# main.net
KiCad netlist of a schematic drawn in EAGLE
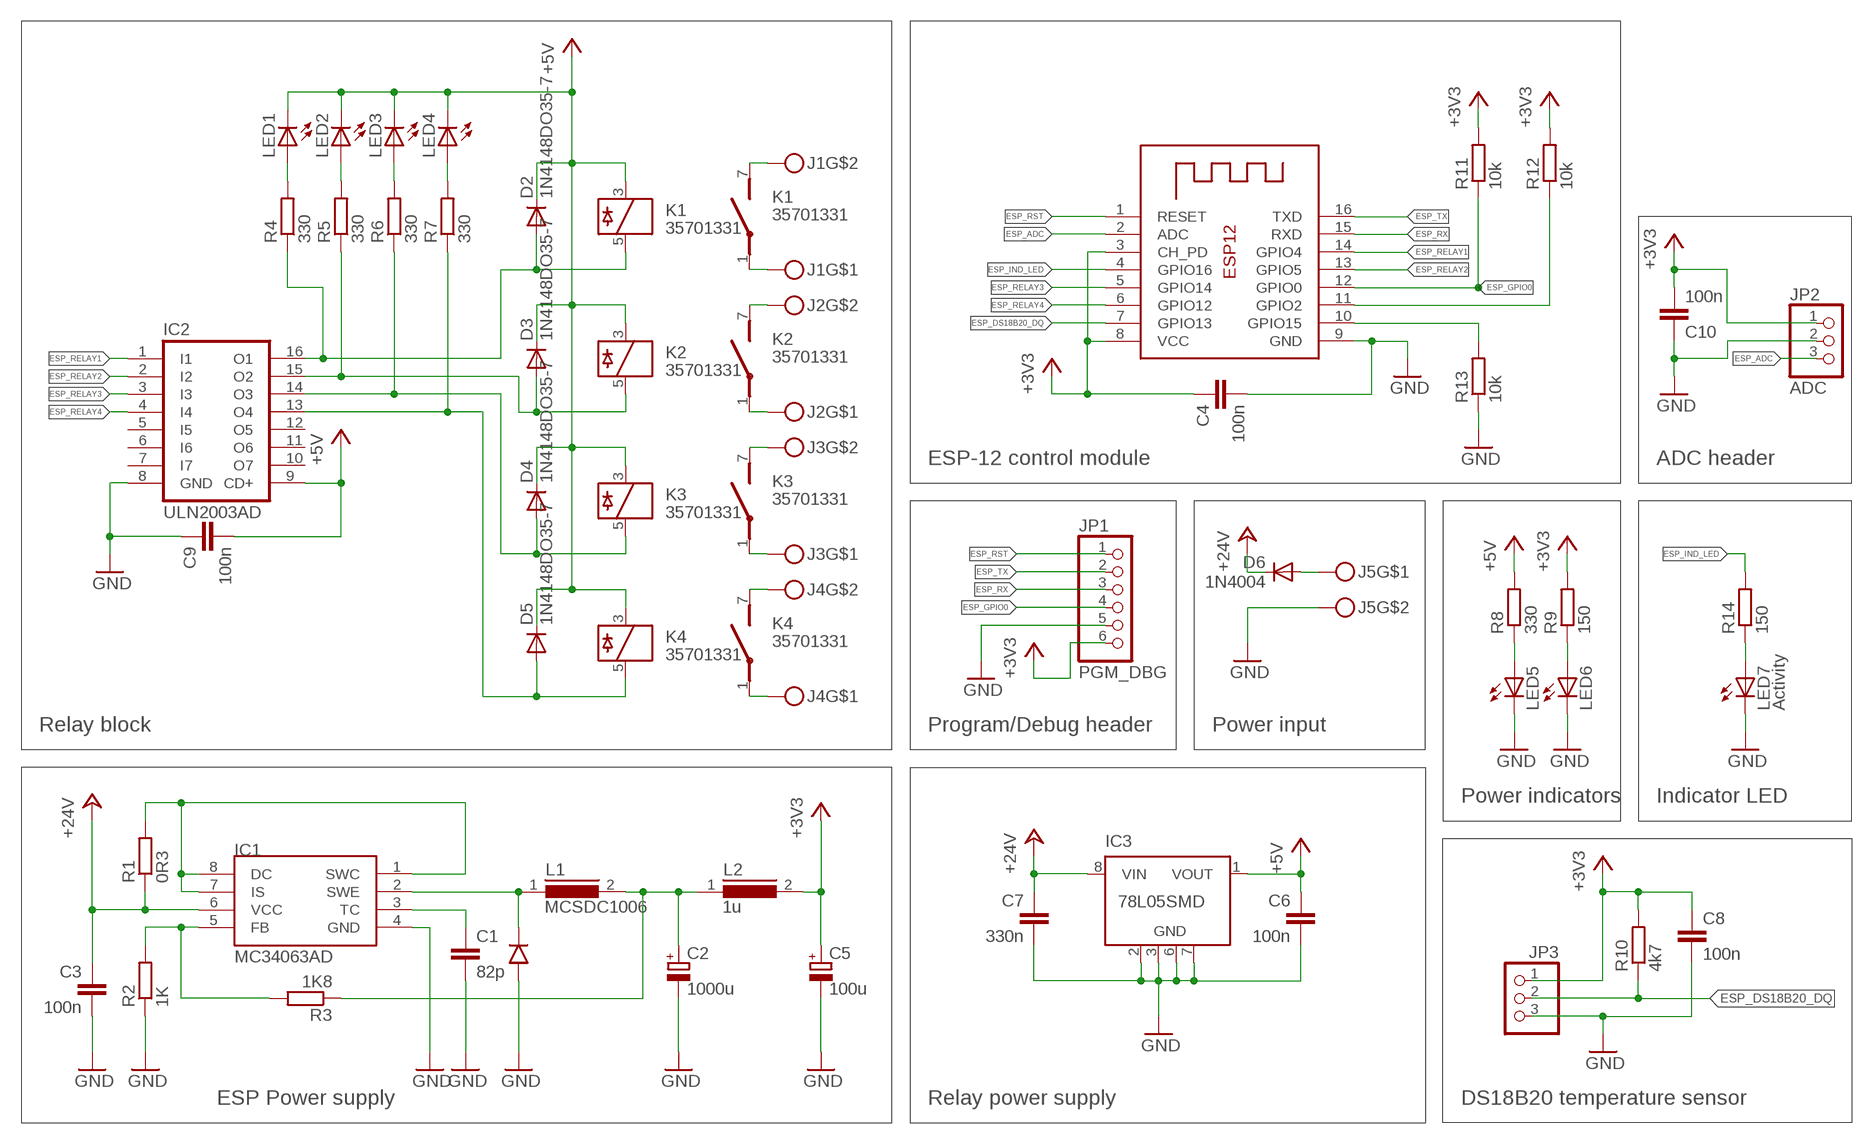
[diagram p0: schematic, sheet 1]

(export (version "E")
  (design (tool "Eeschema 10.0.6"))
  (components
    (comp (ref "C1")
      (value "82p")
      (footprint "eagle-import:C1206")
      (libsource (lib "eagle-import") (part "C-EUC1206"))
    )
    (comp (ref "C2")
      (value "1000u")
      (footprint "eagle-import:UD-10X10_NICHICON")
      (libsource (lib "eagle-import") (part "CPOL-EUUD-10X10"))
    )
    (comp (ref "C3")
      (value "100n")
      (footprint "eagle-import:C1206")
      (libsource (lib "eagle-import") (part "C-EUC1206"))
    )
    (comp (ref "C4")
      (value "100n")
      (footprint "eagle-import:C1206")
      (libsource (lib "eagle-import") (part "C-EUC1206"))
    )
    (comp (ref "C5")
      (value "100u")
      (footprint "eagle-import:153CLV-0807")
      (libsource (lib "eagle-import") (part "CPOL-EU153CLV-0807"))
    )
    (comp (ref "C6")
      (value "100n")
      (footprint "eagle-import:C1206")
      (libsource (lib "eagle-import") (part "C-EUC1206"))
    )
    (comp (ref "C7")
      (value "330n")
      (footprint "eagle-import:C1206")
      (libsource (lib "eagle-import") (part "C-EUC1206"))
    )
    (comp (ref "C8")
      (value "100n")
      (footprint "eagle-import:C1206")
      (libsource (lib "eagle-import") (part "C-EUC1206"))
    )
    (comp (ref "C9")
      (value "100n")
      (footprint "eagle-import:C1206")
      (libsource (lib "eagle-import") (part "C-EUC1206"))
    )
    (comp (ref "C10")
      (value "100n")
      (footprint "eagle-import:C1206")
      (libsource (lib "eagle-import") (part "C-EUC1206"))
    )
    (comp (ref "D1")
      (value "1N5819HW")
      (footprint "eagle-import:SOD123")
      (fields (field (name "MF") "DIODES INC.") (field (name "MPN") "1N5819HW-7-F"))
      (libsource (lib "eagle-import") (part "1N5819HW"))
    )
    (comp (ref "D2")
      (value "1N4148DO35-7")
      (footprint "eagle-import:DO35-7")
      (libsource (lib "eagle-import") (part "1N4148DO35-7"))
    )
    (comp (ref "D3")
      (value "1N4148DO35-7")
      (footprint "eagle-import:DO35-7")
      (libsource (lib "eagle-import") (part "1N4148DO35-7"))
    )
    (comp (ref "D4")
      (value "1N4148DO35-7")
      (footprint "eagle-import:DO35-7")
      (libsource (lib "eagle-import") (part "1N4148DO35-7"))
    )
    (comp (ref "D5")
      (value "1N4148DO35-7")
      (footprint "eagle-import:DO35-7")
      (libsource (lib "eagle-import") (part "1N4148DO35-7"))
    )
    (comp (ref "D6")
      (value "1N4004")
      (footprint "eagle-import:DO41-10")
      (libsource (lib "eagle-import") (part "1N4004"))
    )
    (comp (ref "IC1")
      (value "MC34063AD")
      (footprint "eagle-import:SOIC8")
      (libsource (lib "eagle-import") (part "MC34063AD"))
    )
    (comp (ref "IC2")
      (value "ULN2003AD")
      (footprint "eagle-import:SO16")
      (libsource (lib "eagle-import") (part "ULN2003AD"))
    )
    (comp (ref "IC3")
      (value "78L05SMD")
      (footprint "eagle-import:SO08")
      (libsource (lib "eagle-import") (part "78LSMD05"))
    )
    (comp (ref "J1")
      (value "SCREW-TERMINAL-2PIN")
      (footprint "eagle-import:PITCH4.3-PIN2")
      (libsource (lib "eagle-import") (part "SCREW-TERMINAL-2PIN"))
    )
    (comp (ref "J2")
      (value "SCREW-TERMINAL-2PIN")
      (footprint "eagle-import:PITCH4.3-PIN2")
      (libsource (lib "eagle-import") (part "SCREW-TERMINAL-2PIN"))
    )
    (comp (ref "J3")
      (value "SCREW-TERMINAL-2PIN")
      (footprint "eagle-import:PITCH4.3-PIN2")
      (libsource (lib "eagle-import") (part "SCREW-TERMINAL-2PIN"))
    )
    (comp (ref "J4")
      (value "SCREW-TERMINAL-2PIN")
      (footprint "eagle-import:PITCH4.3-PIN2")
      (libsource (lib "eagle-import") (part "SCREW-TERMINAL-2PIN"))
    )
    (comp (ref "J5")
      (value "PWR_IN")
      (footprint "eagle-import:PITCH4.3-PIN2")
      (libsource (lib "eagle-import") (part "SCREW-TERMINAL-2PIN"))
    )
    (comp (ref "JP1")
      (value "PGM_DBG")
      (footprint "eagle-import:1X06")
      (libsource (lib "eagle-import") (part "PINHD-1X6"))
    )
    (comp (ref "JP2")
      (value "ADC")
      (footprint "eagle-import:1X03")
      (libsource (lib "eagle-import") (part "PINHD-1X3"))
    )
    (comp (ref "JP3")
      (value "PINHD-1X3")
      (footprint "eagle-import:1X03")
      (libsource (lib "eagle-import") (part "PINHD-1X3"))
    )
    (comp (ref "K1")
      (value "35701331")
      (footprint "eagle-import:REED")
      (libsource (lib "eagle-import") (part "35701331"))
    )
    (comp (ref "K2")
      (value "35701331")
      (footprint "eagle-import:REED")
      (libsource (lib "eagle-import") (part "35701331"))
    )
    (comp (ref "K3")
      (value "35701331")
      (footprint "eagle-import:REED")
      (libsource (lib "eagle-import") (part "35701331"))
    )
    (comp (ref "K4")
      (value "35701331")
      (footprint "eagle-import:REED")
      (libsource (lib "eagle-import") (part "35701331"))
    )
    (comp (ref "L1")
      (value "MCSDC1006")
      (footprint "eagle-import:SMD")
      (libsource (lib "eagle-import") (part "MCSDC1006"))
    )
    (comp (ref "L2")
      (value "1u")
      (footprint "eagle-import:R1210")
      (libsource (lib "eagle-import") (part "SMD1210"))
    )
    (comp (ref "LED1")
      (value "LED5MM")
      (footprint "eagle-import:LED5MM")
      (libsource (lib "eagle-import") (part "LED5MM"))
    )
    (comp (ref "LED2")
      (value "LED5MM")
      (footprint "eagle-import:LED5MM")
      (libsource (lib "eagle-import") (part "LED5MM"))
    )
    (comp (ref "LED3")
      (value "LED5MM")
      (footprint "eagle-import:LED5MM")
      (libsource (lib "eagle-import") (part "LED5MM"))
    )
    (comp (ref "LED4")
      (value "LED5MM")
      (footprint "eagle-import:LED5MM")
      (libsource (lib "eagle-import") (part "LED5MM"))
    )
    (comp (ref "LED5")
      (value "LED5MM")
      (footprint "eagle-import:LED5MM")
      (libsource (lib "eagle-import") (part "LED5MM"))
    )
    (comp (ref "LED6")
      (value "LED5MM")
      (footprint "eagle-import:LED5MM")
      (libsource (lib "eagle-import") (part "LED5MM"))
    )
    (comp (ref "LED7")
      (value "Activity")
      (footprint "eagle-import:LED5MM")
      (libsource (lib "eagle-import") (part "LED5MM"))
    )
    (comp (ref "R1")
      (value "0R3")
      (footprint "eagle-import:R1206")
      (libsource (lib "eagle-import") (part "R-EU_R1206"))
    )
    (comp (ref "R2")
      (value "1K")
      (footprint "eagle-import:R1206")
      (libsource (lib "eagle-import") (part "R-EU_R1206"))
    )
    (comp (ref "R3")
      (value "1K8")
      (footprint "eagle-import:R1206")
      (libsource (lib "eagle-import") (part "R-EU_R1206"))
    )
    (comp (ref "R4")
      (value "330")
      (footprint "eagle-import:R1206")
      (libsource (lib "eagle-import") (part "R-EU_R1206"))
    )
    (comp (ref "R5")
      (value "330")
      (footprint "eagle-import:R1206")
      (libsource (lib "eagle-import") (part "R-EU_R1206"))
    )
    (comp (ref "R6")
      (value "330")
      (footprint "eagle-import:R1206")
      (libsource (lib "eagle-import") (part "R-EU_R1206"))
    )
    (comp (ref "R7")
      (value "330")
      (footprint "eagle-import:R1206")
      (libsource (lib "eagle-import") (part "R-EU_R1206"))
    )
    (comp (ref "R8")
      (value "330")
      (footprint "eagle-import:R1206")
      (libsource (lib "eagle-import") (part "R-EU_R1206"))
    )
    (comp (ref "R9")
      (value "150")
      (footprint "eagle-import:R1206")
      (libsource (lib "eagle-import") (part "R-EU_R1206"))
    )
    (comp (ref "R10")
      (value "4k7")
      (footprint "eagle-import:R1206")
      (libsource (lib "eagle-import") (part "R-EU_R1206"))
    )
    (comp (ref "R11")
      (value "10k")
      (footprint "eagle-import:R1206")
      (libsource (lib "eagle-import") (part "R-EU_R1206"))
    )
    (comp (ref "R12")
      (value "10k")
      (footprint "eagle-import:R1206")
      (libsource (lib "eagle-import") (part "R-EU_R1206"))
    )
    (comp (ref "R13")
      (value "10k")
      (footprint "eagle-import:R1206")
      (libsource (lib "eagle-import") (part "R-EU_R1206"))
    )
    (comp (ref "R14")
      (value "150")
      (footprint "eagle-import:R1206")
      (libsource (lib "eagle-import") (part "R-EU_R1206"))
    )
    (comp (ref "X1")
      (value "ESP-12")
      (footprint "eagle-import:ESP-12")
      (libsource (lib "eagle-import") (part "ESP-12"))
    )
  )
  (nets
    (net (code "1") (name "+3V3") (class "Default")
      (node (ref "C10") (pin "2") (pinfunction "2_2") (pintype "passive"))
      (node (ref "C4") (pin "1") (pinfunction "1_1") (pintype "passive"))
      (node (ref "C5") (pin "+") (pinfunction "+_+") (pintype "passive"))
      (node (ref "C8") (pin "1") (pinfunction "1_1") (pintype "passive"))
      (node (ref "JP1") (pin "6") (pinfunction "6_6") (pintype "passive"))
      (node (ref "JP2") (pin "1") (pinfunction "1_1") (pintype "passive"))
      (node (ref "JP3") (pin "1") (pinfunction "1_1") (pintype "passive"))
      (node (ref "L2") (pin "2") (pinfunction "2_2") (pintype "passive"))
      (node (ref "R10") (pin "2") (pinfunction "2_2") (pintype "passive"))
      (node (ref "R11") (pin "2") (pinfunction "2_2") (pintype "passive"))
      (node (ref "R12") (pin "2") (pinfunction "2_2") (pintype "passive"))
      (node (ref "R9") (pin "2") (pinfunction "2_2") (pintype "passive"))
      (node (ref "X1") (pin "3") (pinfunction "CH_PD_3") (pintype "input"))
      (node (ref "X1") (pin "8") (pinfunction "VCC_8") (pintype "power_in"))
    )
    (net (code "2") (name "+5V") (class "Default")
      (node (ref "C6") (pin "1") (pinfunction "1_1") (pintype "passive"))
      (node (ref "C9") (pin "2") (pinfunction "2_2") (pintype "passive"))
      (node (ref "D2") (pin "C") (pinfunction "C_C") (pintype "passive"))
      (node (ref "D3") (pin "C") (pinfunction "C_C") (pintype "passive"))
      (node (ref "D4") (pin "C") (pinfunction "C_C") (pintype "passive"))
      (node (ref "D5") (pin "C") (pinfunction "C_C") (pintype "passive"))
      (node (ref "IC2") (pin "9") (pinfunction "CD+_9") (pintype "passive"))
      (node (ref "IC3") (pin "1") (pinfunction "VOUT_1") (pintype "output"))
      (node (ref "K1") (pin "3") (pinfunction "3_3") (pintype "passive"))
      (node (ref "K2") (pin "3") (pinfunction "3_3") (pintype "passive"))
      (node (ref "K3") (pin "3") (pinfunction "3_3") (pintype "passive"))
      (node (ref "K4") (pin "3") (pinfunction "3_3") (pintype "passive"))
      (node (ref "LED1") (pin "K") (pinfunction "C_K") (pintype "passive"))
      (node (ref "LED2") (pin "K") (pinfunction "C_K") (pintype "passive"))
      (node (ref "LED3") (pin "K") (pinfunction "C_K") (pintype "passive"))
      (node (ref "LED4") (pin "K") (pinfunction "C_K") (pintype "passive"))
      (node (ref "R8") (pin "2") (pinfunction "2_2") (pintype "passive"))
    )
    (net (code "3") (name "+24V") (class "Default")
      (node (ref "C3") (pin "1") (pinfunction "1_1") (pintype "passive"))
      (node (ref "C7") (pin "1") (pinfunction "1_1") (pintype "passive"))
      (node (ref "D6") (pin "C") (pinfunction "C_C") (pintype "passive"))
      (node (ref "IC1") (pin "6") (pinfunction "VCC_6") (pintype "passive"))
      (node (ref "IC3") (pin "8") (pinfunction "VIN_8") (pintype "passive"))
      (node (ref "R1") (pin "1") (pinfunction "1_1") (pintype "passive"))
    )
    (net (code "4") (name "ESP_ADC") (class "Default")
      (node (ref "JP2") (pin "3") (pinfunction "3_3") (pintype "passive"))
      (node (ref "X1") (pin "2") (pinfunction "ADC_2") (pintype "passive"))
    )
    (net (code "5") (name "ESP_DS18B20_DQ") (class "Default")
      (node (ref "JP3") (pin "2") (pinfunction "2_2") (pintype "passive"))
      (node (ref "R10") (pin "1") (pinfunction "1_1") (pintype "passive"))
      (node (ref "X1") (pin "7") (pinfunction "GPIO13_7") (pintype "bidirectional"))
    )
    (net (code "6") (name "ESP_GPIO0") (class "Default")
      (node (ref "JP1") (pin "4") (pinfunction "4_4") (pintype "passive"))
      (node (ref "R11") (pin "1") (pinfunction "1_1") (pintype "passive"))
      (node (ref "X1") (pin "12") (pinfunction "GPIO0_12") (pintype "bidirectional"))
    )
    (net (code "7") (name "ESP_IND_LED") (class "Default")
      (node (ref "R14") (pin "2") (pinfunction "2_2") (pintype "passive"))
      (node (ref "X1") (pin "4") (pinfunction "GPIO16_4") (pintype "bidirectional"))
    )
    (net (code "8") (name "ESP_RELAY1") (class "Default")
      (node (ref "IC2") (pin "1") (pinfunction "I1_1") (pintype "input"))
      (node (ref "X1") (pin "14") (pinfunction "GPIO4_14") (pintype "bidirectional"))
    )
    (net (code "9") (name "ESP_RELAY2") (class "Default")
      (node (ref "IC2") (pin "2") (pinfunction "I2_2") (pintype "input"))
      (node (ref "X1") (pin "13") (pinfunction "GPIO5_13") (pintype "bidirectional"))
    )
    (net (code "10") (name "ESP_RELAY3") (class "Default")
      (node (ref "IC2") (pin "3") (pinfunction "I3_3") (pintype "input"))
      (node (ref "X1") (pin "5") (pinfunction "GPIO14_5") (pintype "bidirectional"))
    )
    (net (code "11") (name "ESP_RELAY4") (class "Default")
      (node (ref "IC2") (pin "4") (pinfunction "I4_4") (pintype "input"))
      (node (ref "X1") (pin "6") (pinfunction "GPIO12_6") (pintype "bidirectional"))
    )
    (net (code "12") (name "ESP_RST") (class "Default")
      (node (ref "JP1") (pin "1") (pinfunction "1_1") (pintype "passive"))
      (node (ref "X1") (pin "1") (pinfunction "RESET_1") (pintype "input"))
    )
    (net (code "13") (name "ESP_RX") (class "Default")
      (node (ref "JP1") (pin "3") (pinfunction "3_3") (pintype "passive"))
      (node (ref "X1") (pin "15") (pinfunction "RXD_15") (pintype "input"))
    )
    (net (code "14") (name "ESP_TX") (class "Default")
      (node (ref "JP1") (pin "2") (pinfunction "2_2") (pintype "passive"))
      (node (ref "X1") (pin "16") (pinfunction "TXD_16") (pintype "output"))
    )
    (net (code "15") (name "GND") (class "Default")
      (node (ref "C1") (pin "2") (pinfunction "2_2") (pintype "passive"))
      (node (ref "C10") (pin "1") (pinfunction "1_1") (pintype "passive"))
      (node (ref "C2") (pin "-") (pinfunction "-_-") (pintype "passive"))
      (node (ref "C3") (pin "2") (pinfunction "2_2") (pintype "passive"))
      (node (ref "C4") (pin "2") (pinfunction "2_2") (pintype "passive"))
      (node (ref "C5") (pin "-") (pinfunction "-_-") (pintype "passive"))
      (node (ref "C6") (pin "2") (pinfunction "2_2") (pintype "passive"))
      (node (ref "C7") (pin "2") (pinfunction "2_2") (pintype "passive"))
      (node (ref "C8") (pin "2") (pinfunction "2_2") (pintype "passive"))
      (node (ref "C9") (pin "1") (pinfunction "1_1") (pintype "passive"))
      (node (ref "D1") (pin "A") (pinfunction "A_A") (pintype "passive"))
      (node (ref "IC1") (pin "4") (pinfunction "GND_4") (pintype "passive"))
      (node (ref "IC2") (pin "8") (pinfunction "GND_8") (pintype "power_in"))
      (node (ref "IC3") (pin "2") (pinfunction "GND_2") (pintype "power_in"))
      (node (ref "IC3") (pin "3") (pinfunction "GND_3") (pintype "power_in"))
      (node (ref "IC3") (pin "6") (pinfunction "GND_6") (pintype "power_in"))
      (node (ref "IC3") (pin "7") (pinfunction "GND_7") (pintype "power_in"))
      (node (ref "J5") (pin "2") (pinfunction "KL_2") (pintype "passive"))
      (node (ref "JP1") (pin "5") (pinfunction "5_5") (pintype "passive"))
      (node (ref "JP2") (pin "2") (pinfunction "2_2") (pintype "passive"))
      (node (ref "JP3") (pin "3") (pinfunction "3_3") (pintype "passive"))
      (node (ref "LED5") (pin "K") (pinfunction "C_K") (pintype "passive"))
      (node (ref "LED6") (pin "K") (pinfunction "C_K") (pintype "passive"))
      (node (ref "LED7") (pin "K") (pinfunction "C_K") (pintype "passive"))
      (node (ref "R13") (pin "1") (pinfunction "1_1") (pintype "passive"))
      (node (ref "R2") (pin "1") (pinfunction "1_1") (pintype "passive"))
      (node (ref "X1") (pin "9") (pinfunction "GND_9") (pintype "power_in"))
    )
    (net (code "16") (name "Net-(C2-Pad+)") (class "Default")
      (node (ref "C2") (pin "+") (pinfunction "+_+") (pintype "passive"))
      (node (ref "L1") (pin "2") (pinfunction "2_2") (pintype "passive"))
      (node (ref "L2") (pin "1") (pinfunction "1_1") (pintype "passive"))
      (node (ref "R3") (pin "1") (pinfunction "1_1") (pintype "passive"))
    )
    (net (code "17") (name "Net-(IC1-DC)") (class "Default")
      (node (ref "IC1") (pin "1") (pinfunction "SWC_1") (pintype "passive"))
      (node (ref "IC1") (pin "7") (pinfunction "IS_7") (pintype "passive"))
      (node (ref "IC1") (pin "8") (pinfunction "DC_8") (pintype "passive"))
      (node (ref "R1") (pin "2") (pinfunction "2_2") (pintype "passive"))
    )
    (net (code "18") (name "Net-(IC1-FB)") (class "Default")
      (node (ref "IC1") (pin "5") (pinfunction "FB_5") (pintype "passive"))
      (node (ref "R2") (pin "2") (pinfunction "2_2") (pintype "passive"))
      (node (ref "R3") (pin "2") (pinfunction "2_2") (pintype "passive"))
    )
    (net (code "19") (name "Net-(IC1-SWE)") (class "Default")
      (node (ref "D1") (pin "C") (pinfunction "C_C") (pintype "passive"))
      (node (ref "IC1") (pin "2") (pinfunction "SWE_2") (pintype "passive"))
      (node (ref "L1") (pin "1") (pinfunction "1_1") (pintype "passive"))
    )
    (net (code "20") (name "Net-(IC1-TC)") (class "Default")
      (node (ref "C1") (pin "1") (pinfunction "1_1") (pintype "passive"))
      (node (ref "IC1") (pin "3") (pinfunction "TC_3") (pintype "passive"))
    )
    (net (code "21") (name "Net-(IC2-O1)") (class "Default")
      (node (ref "D2") (pin "A") (pinfunction "A_A") (pintype "passive"))
      (node (ref "IC2") (pin "16") (pinfunction "O1_16") (pintype "open_collector"))
      (node (ref "K1") (pin "5") (pinfunction "5_5") (pintype "passive"))
      (node (ref "R4") (pin "1") (pinfunction "1_1") (pintype "passive"))
    )
    (net (code "22") (name "Net-(IC2-O2)") (class "Default")
      (node (ref "D3") (pin "A") (pinfunction "A_A") (pintype "passive"))
      (node (ref "IC2") (pin "15") (pinfunction "O2_15") (pintype "open_collector"))
      (node (ref "K2") (pin "5") (pinfunction "5_5") (pintype "passive"))
      (node (ref "R5") (pin "1") (pinfunction "1_1") (pintype "passive"))
    )
    (net (code "23") (name "Net-(IC2-O3)") (class "Default")
      (node (ref "D4") (pin "A") (pinfunction "A_A") (pintype "passive"))
      (node (ref "IC2") (pin "14") (pinfunction "O3_14") (pintype "open_collector"))
      (node (ref "K3") (pin "5") (pinfunction "5_5") (pintype "passive"))
      (node (ref "R6") (pin "1") (pinfunction "1_1") (pintype "passive"))
    )
    (net (code "24") (name "Net-(IC2-O4)") (class "Default")
      (node (ref "D5") (pin "A") (pinfunction "A_A") (pintype "passive"))
      (node (ref "IC2") (pin "13") (pinfunction "O4_13") (pintype "open_collector"))
      (node (ref "K4") (pin "5") (pinfunction "5_5") (pintype "passive"))
      (node (ref "R7") (pin "1") (pinfunction "1_1") (pintype "passive"))
    )
    (net (code "25") (name "Net-(J1A-KL)") (class "Default")
      (node (ref "J1") (pin "1") (pinfunction "KL_1") (pintype "passive"))
      (node (ref "K1") (pin "1") (pinfunction "P_1") (pintype "passive"))
    )
    (net (code "26") (name "Net-(J1B-KL)") (class "Default")
      (node (ref "J1") (pin "2") (pinfunction "KL_2") (pintype "passive"))
      (node (ref "K1") (pin "7") (pinfunction "S_7") (pintype "passive"))
    )
    (net (code "27") (name "Net-(J2A-KL)") (class "Default")
      (node (ref "J2") (pin "1") (pinfunction "KL_1") (pintype "passive"))
      (node (ref "K2") (pin "1") (pinfunction "P_1") (pintype "passive"))
    )
    (net (code "28") (name "Net-(J2B-KL)") (class "Default")
      (node (ref "J2") (pin "2") (pinfunction "KL_2") (pintype "passive"))
      (node (ref "K2") (pin "7") (pinfunction "S_7") (pintype "passive"))
    )
    (net (code "29") (name "Net-(J3A-KL)") (class "Default")
      (node (ref "J3") (pin "1") (pinfunction "KL_1") (pintype "passive"))
      (node (ref "K3") (pin "1") (pinfunction "P_1") (pintype "passive"))
    )
    (net (code "30") (name "Net-(J3B-KL)") (class "Default")
      (node (ref "J3") (pin "2") (pinfunction "KL_2") (pintype "passive"))
      (node (ref "K3") (pin "7") (pinfunction "S_7") (pintype "passive"))
    )
    (net (code "31") (name "Net-(J4A-KL)") (class "Default")
      (node (ref "J4") (pin "1") (pinfunction "KL_1") (pintype "passive"))
      (node (ref "K4") (pin "1") (pinfunction "P_1") (pintype "passive"))
    )
    (net (code "32") (name "Net-(J4B-KL)") (class "Default")
      (node (ref "J4") (pin "2") (pinfunction "KL_2") (pintype "passive"))
      (node (ref "K4") (pin "7") (pinfunction "S_7") (pintype "passive"))
    )
    (net (code "33") (name "Net-(J5A-KL)") (class "Default")
      (node (ref "D6") (pin "A") (pinfunction "A_A") (pintype "passive"))
      (node (ref "J5") (pin "1") (pinfunction "KL_1") (pintype "passive"))
    )
    (net (code "34") (name "Net-(LED1-PadA)") (class "Default")
      (node (ref "LED1") (pin "A") (pinfunction "A_A") (pintype "passive"))
      (node (ref "R4") (pin "2") (pinfunction "2_2") (pintype "passive"))
    )
    (net (code "35") (name "Net-(LED2-PadA)") (class "Default")
      (node (ref "LED2") (pin "A") (pinfunction "A_A") (pintype "passive"))
      (node (ref "R5") (pin "2") (pinfunction "2_2") (pintype "passive"))
    )
    (net (code "36") (name "Net-(LED3-PadA)") (class "Default")
      (node (ref "LED3") (pin "A") (pinfunction "A_A") (pintype "passive"))
      (node (ref "R6") (pin "2") (pinfunction "2_2") (pintype "passive"))
    )
    (net (code "37") (name "Net-(LED4-PadA)") (class "Default")
      (node (ref "LED4") (pin "A") (pinfunction "A_A") (pintype "passive"))
      (node (ref "R7") (pin "2") (pinfunction "2_2") (pintype "passive"))
    )
    (net (code "38") (name "Net-(LED5-PadA)") (class "Default")
      (node (ref "LED5") (pin "A") (pinfunction "A_A") (pintype "passive"))
      (node (ref "R8") (pin "1") (pinfunction "1_1") (pintype "passive"))
    )
    (net (code "39") (name "Net-(LED6-PadA)") (class "Default")
      (node (ref "LED6") (pin "A") (pinfunction "A_A") (pintype "passive"))
      (node (ref "R9") (pin "1") (pinfunction "1_1") (pintype "passive"))
    )
    (net (code "40") (name "Net-(LED7-PadA)") (class "Default")
      (node (ref "LED7") (pin "A") (pinfunction "A_A") (pintype "passive"))
      (node (ref "R14") (pin "1") (pinfunction "1_1") (pintype "passive"))
    )
    (net (code "41") (name "Net-(X1-GPIO2)") (class "Default")
      (node (ref "R12") (pin "1") (pinfunction "1_1") (pintype "passive"))
      (node (ref "X1") (pin "11") (pinfunction "GPIO2_11") (pintype "bidirectional"))
    )
    (net (code "42") (name "Net-(X1-GPIO15)") (class "Default")
      (node (ref "R13") (pin "2") (pinfunction "2_2") (pintype "passive"))
      (node (ref "X1") (pin "10") (pinfunction "GPIO15_10") (pintype "bidirectional"))
    )
    (net (code "43") (name "unconnected-(IC2-I5-Pad5)") (class "Default")
      (node (ref "IC2") (pin "5") (pinfunction "I5_5") (pintype "input"))
    )
    (net (code "44") (name "unconnected-(IC2-I6-Pad6)") (class "Default")
      (node (ref "IC2") (pin "6") (pinfunction "I6_6") (pintype "input"))
    )
    (net (code "45") (name "unconnected-(IC2-I7-Pad7)") (class "Default")
      (node (ref "IC2") (pin "7") (pinfunction "I7_7") (pintype "input"))
    )
    (net (code "46") (name "unconnected-(IC2-O5-Pad12)") (class "Default")
      (node (ref "IC2") (pin "12") (pinfunction "O5_12") (pintype "open_collector"))
    )
    (net (code "47") (name "unconnected-(IC2-O6-Pad11)") (class "Default")
      (node (ref "IC2") (pin "11") (pinfunction "O6_11") (pintype "open_collector"))
    )
    (net (code "48") (name "unconnected-(IC2-O7-Pad10)") (class "Default")
      (node (ref "IC2") (pin "10") (pinfunction "O7_10") (pintype "open_collector"))
    )
  )
)
